# magarray-halleffect-v3r0.net
KiCad netlist of a schematic drawn in EAGLE
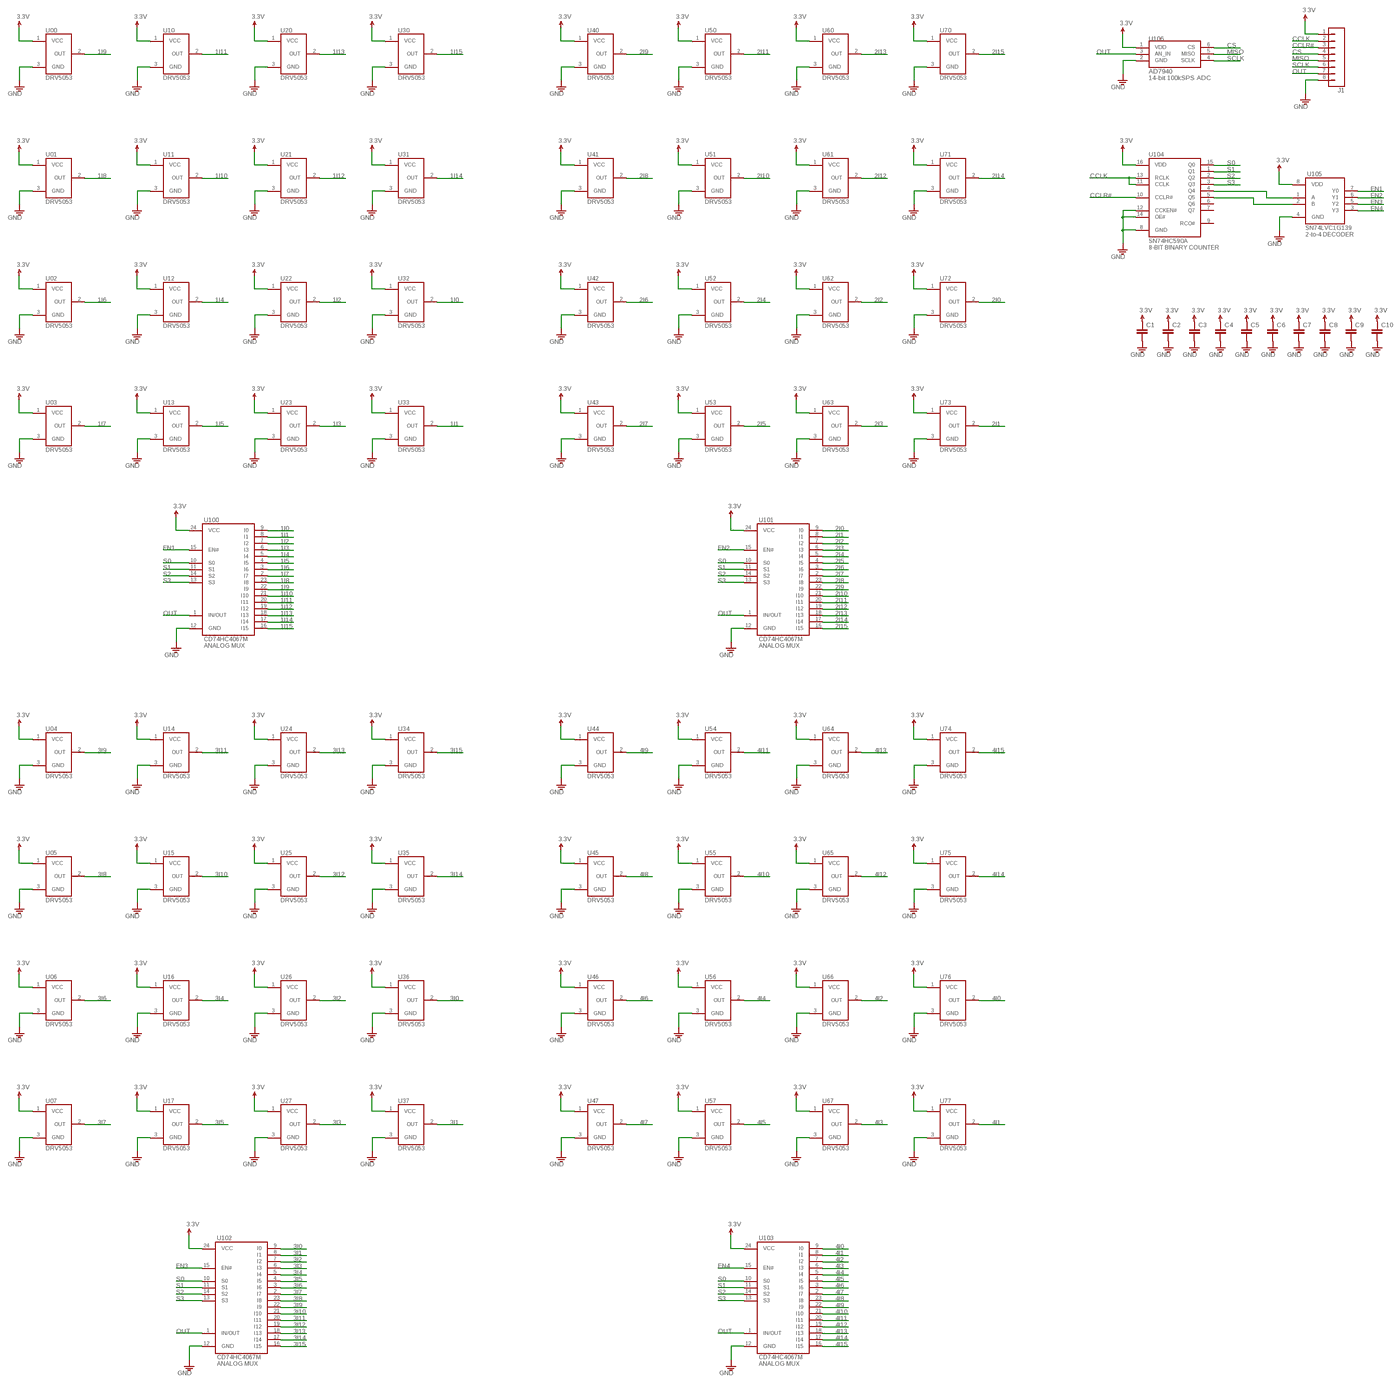
[diagram p0: schematic, sheet 1, overview]
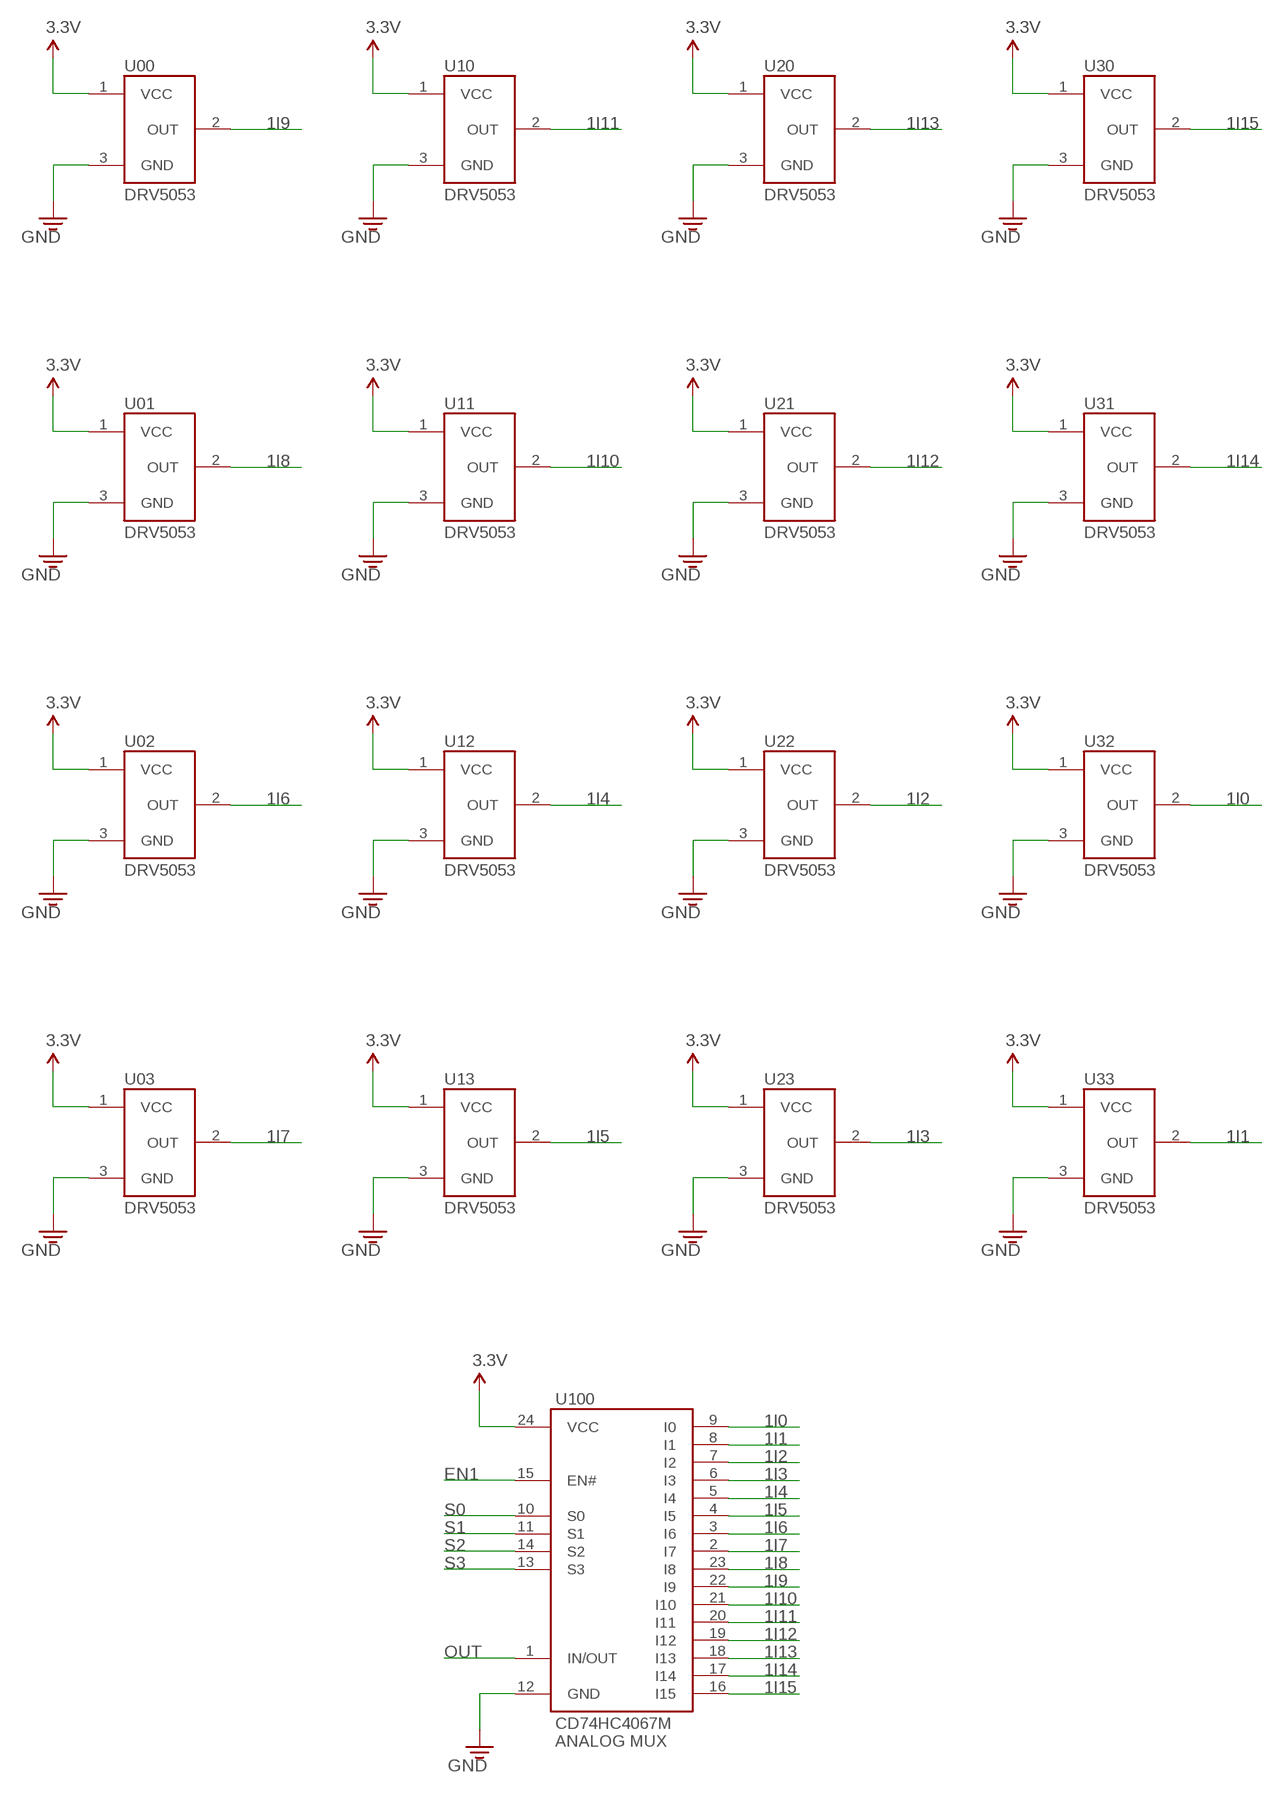
[diagram p1: schematic, sheet 1, part 1 of 4]
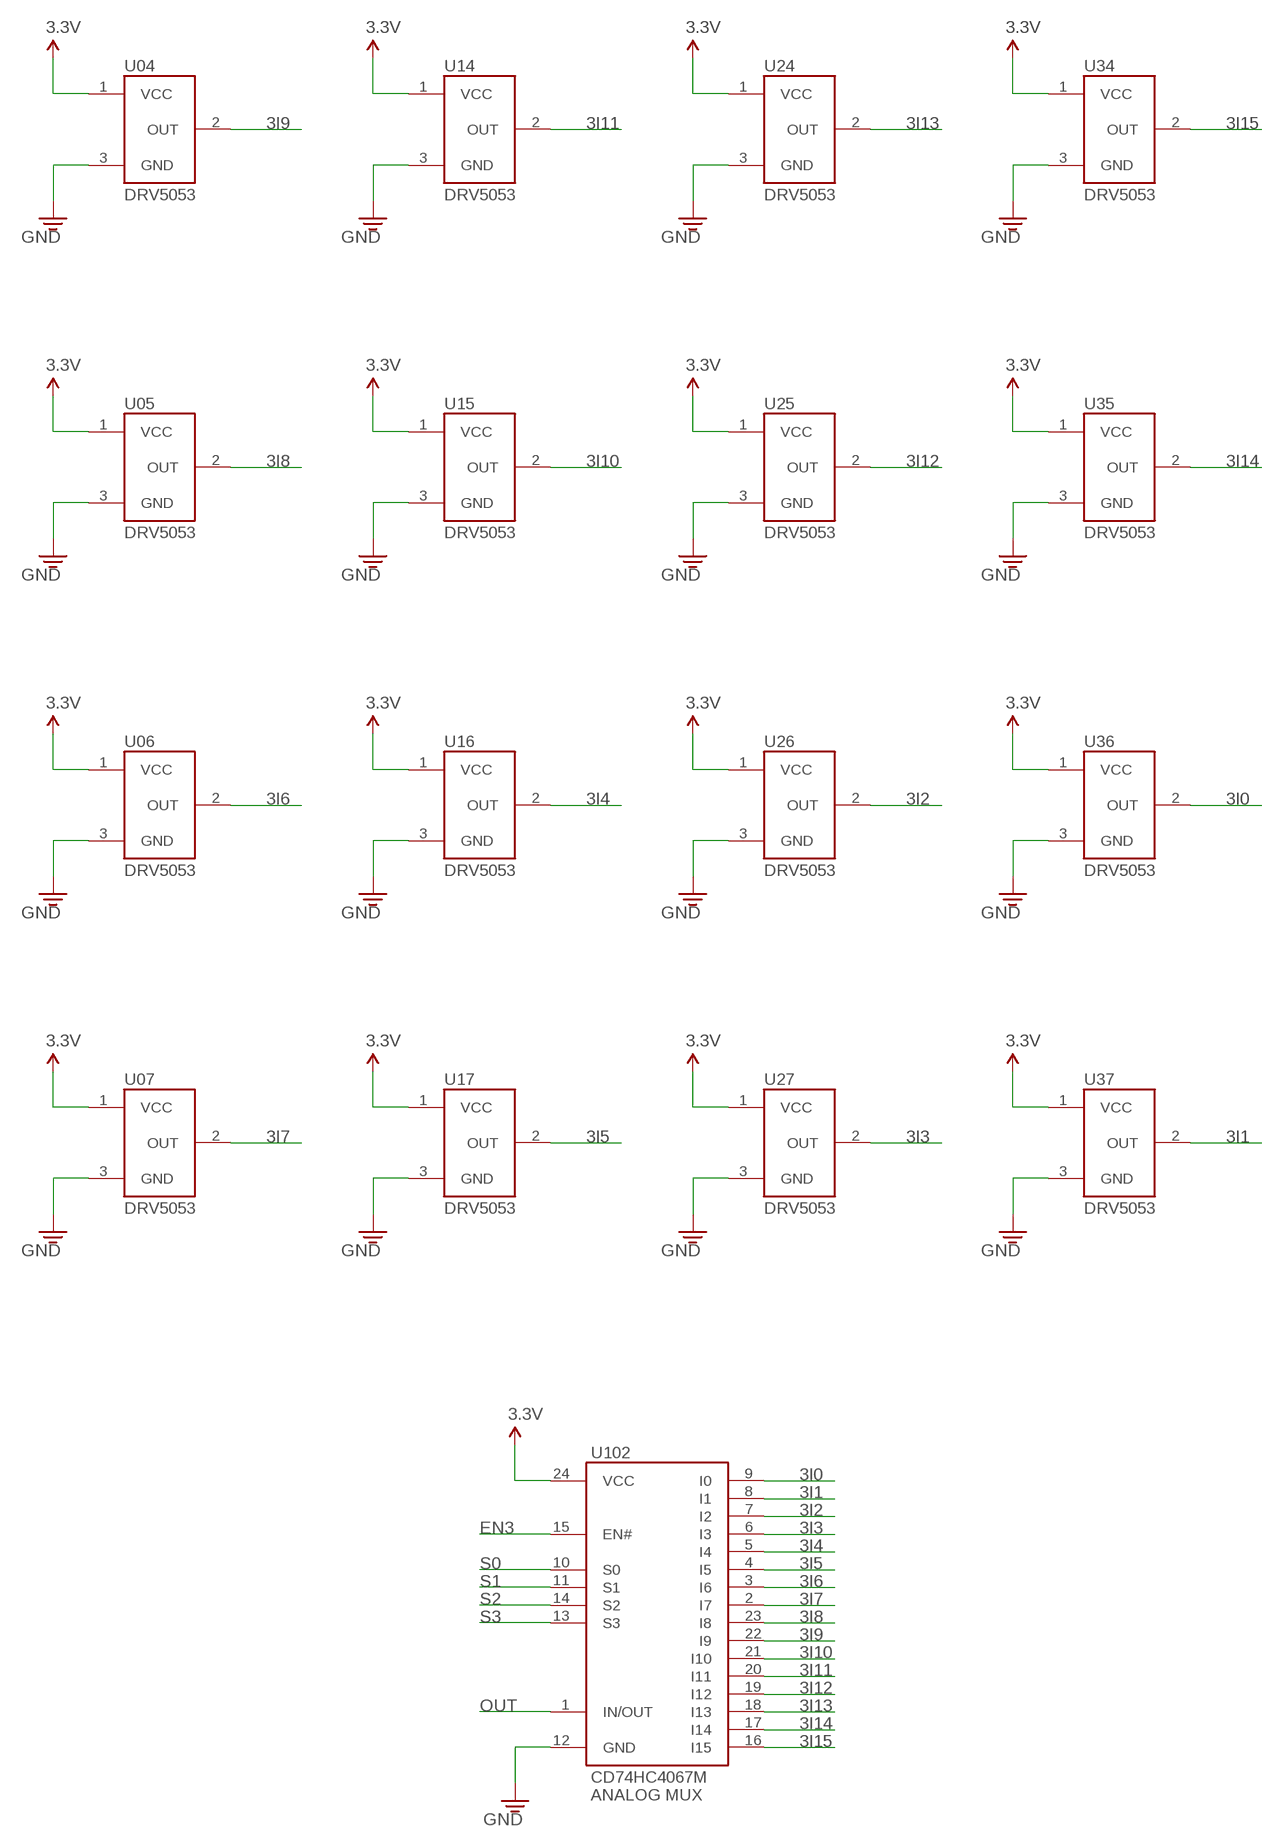
[diagram p2: schematic, sheet 1, part 2 of 4]
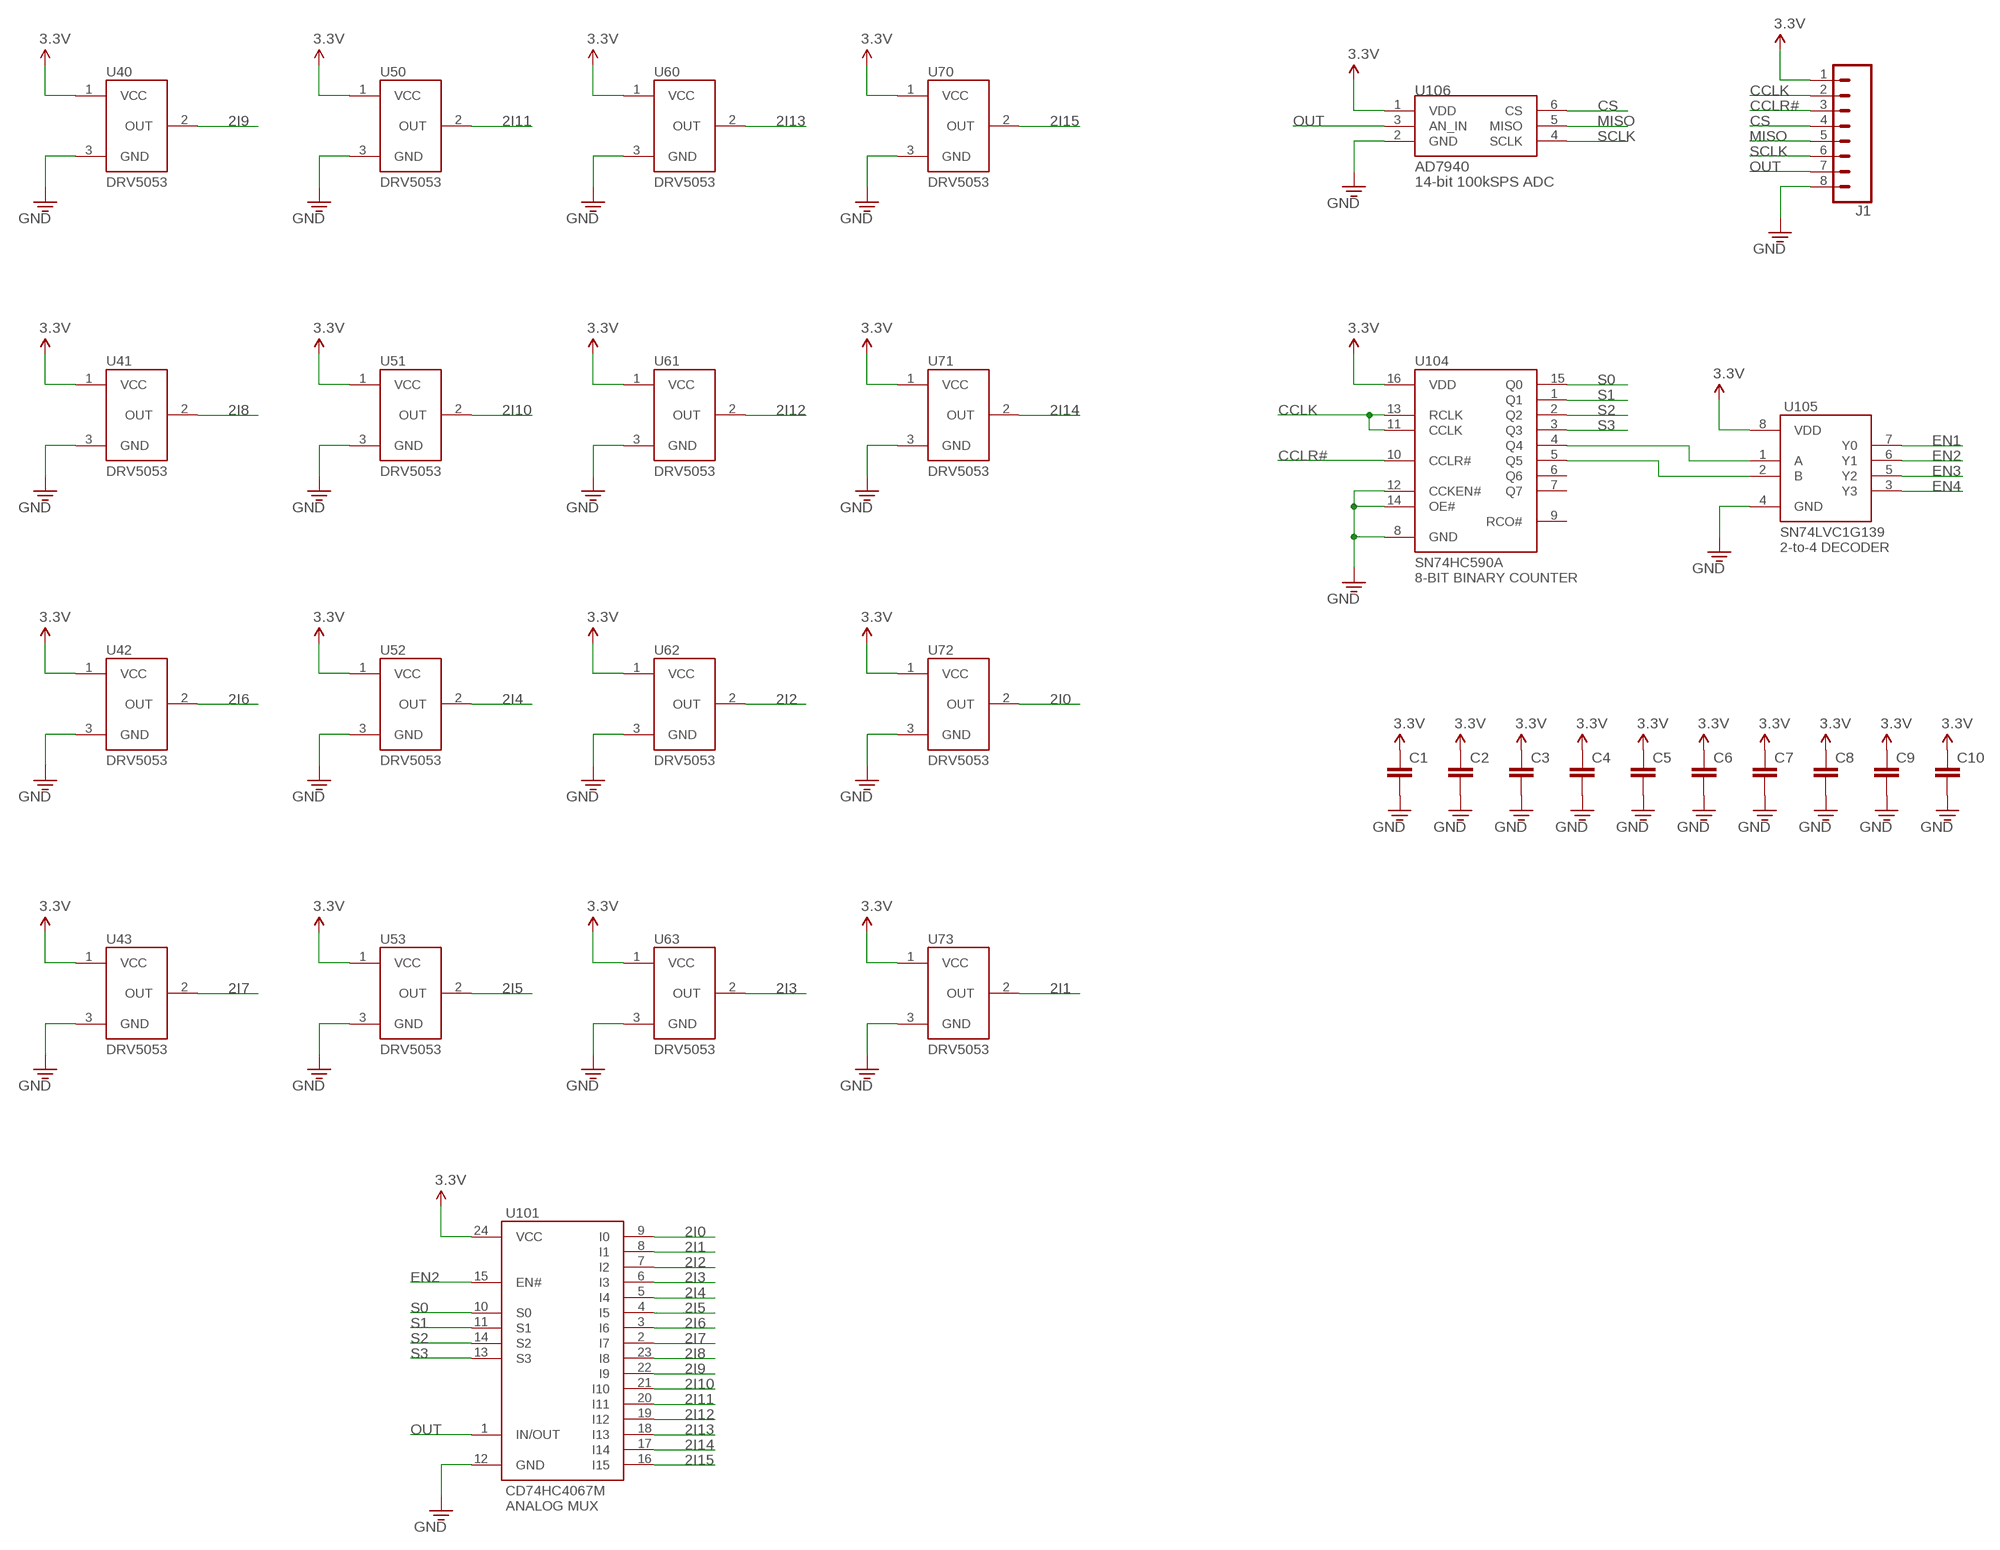
[diagram p3: schematic, sheet 1, part 3 of 4]
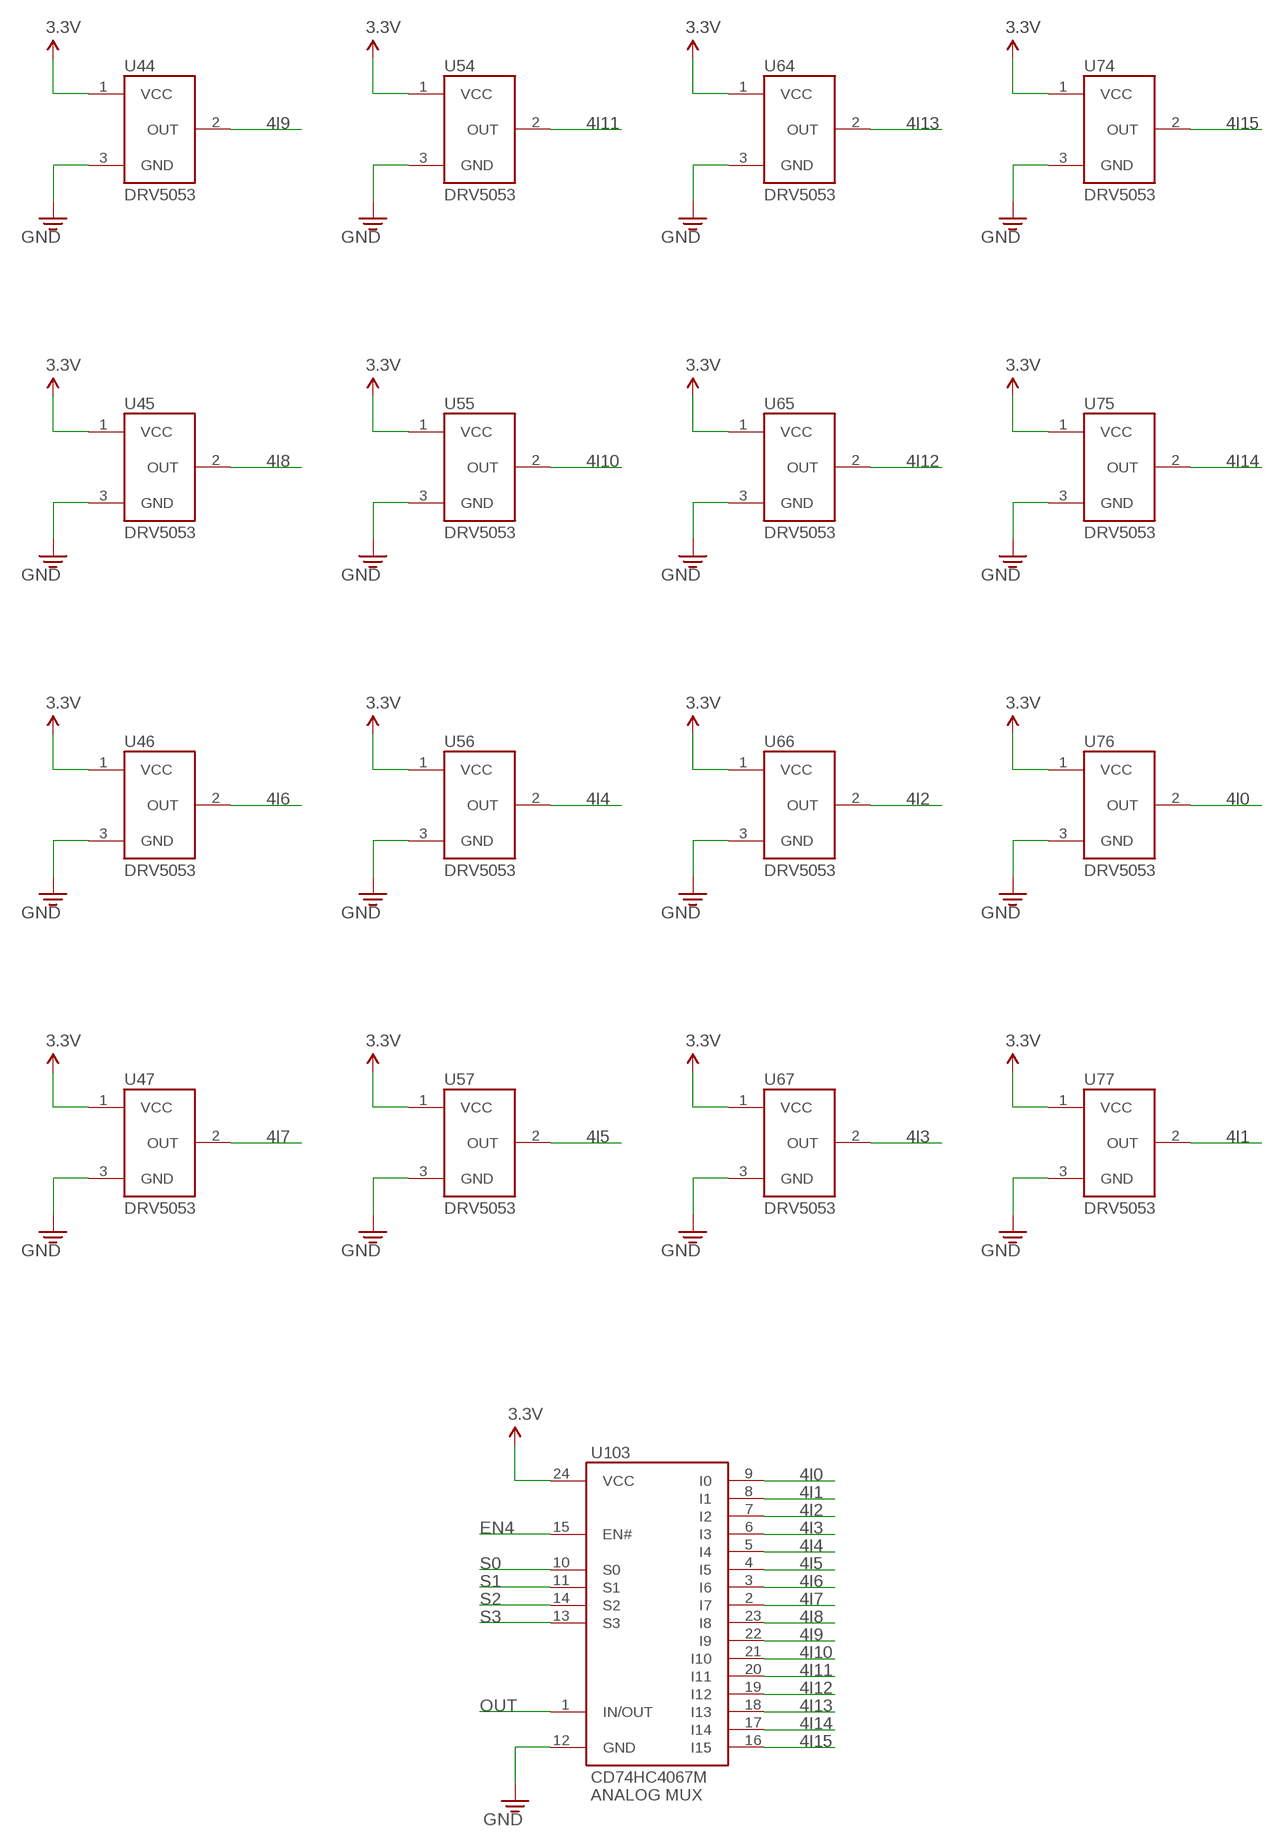
[diagram p4: schematic, sheet 1, part 4 of 4]

(export (version "E")
  (design (tool "Eeschema 10.0.6"))
  (components
    (comp (ref "C1")
      (value "CAP0603")
      (footprint "eagle-import:0603")
      (libsource (lib "eagle-import") (part "CAP0603"))
    )
    (comp (ref "C2")
      (value "CAP0603")
      (footprint "eagle-import:0603")
      (libsource (lib "eagle-import") (part "CAP0603"))
    )
    (comp (ref "C3")
      (value "CAP0603")
      (footprint "eagle-import:0603")
      (libsource (lib "eagle-import") (part "CAP0603"))
    )
    (comp (ref "C4")
      (value "CAP0603")
      (footprint "eagle-import:0603")
      (libsource (lib "eagle-import") (part "CAP0603"))
    )
    (comp (ref "C5")
      (value "CAP0603")
      (footprint "eagle-import:0603")
      (libsource (lib "eagle-import") (part "CAP0603"))
    )
    (comp (ref "C6")
      (value "CAP0603")
      (footprint "eagle-import:0603")
      (libsource (lib "eagle-import") (part "CAP0603"))
    )
    (comp (ref "C7")
      (value "CAP0603")
      (footprint "eagle-import:0603")
      (libsource (lib "eagle-import") (part "CAP0603"))
    )
    (comp (ref "C8")
      (value "CAP0603")
      (footprint "eagle-import:0603")
      (libsource (lib "eagle-import") (part "CAP0603"))
    )
    (comp (ref "C9")
      (value "CAP0603")
      (footprint "eagle-import:0603")
      (libsource (lib "eagle-import") (part "CAP0603"))
    )
    (comp (ref "C10")
      (value "CAP0603")
      (footprint "eagle-import:0603")
      (libsource (lib "eagle-import") (part "CAP0603"))
    )
    (comp (ref "J1")
      (value "CONN_08LOCK_NO_SILK")
      (footprint "eagle-import:1X08_LOCK_NO_SILK")
      (libsource (lib "eagle-import") (part "CONN_08LOCK_NO_SILK"))
    )
    (comp (ref "U00")
      (value "DRV5053")
      (footprint "eagle-import:SOT-23")
      (libsource (lib "eagle-import") (part "DRV5053"))
    )
    (comp (ref "U01")
      (value "DRV5053")
      (footprint "eagle-import:SOT-23")
      (libsource (lib "eagle-import") (part "DRV5053"))
    )
    (comp (ref "U02")
      (value "DRV5053")
      (footprint "eagle-import:SOT-23")
      (libsource (lib "eagle-import") (part "DRV5053"))
    )
    (comp (ref "U03")
      (value "DRV5053")
      (footprint "eagle-import:SOT-23")
      (libsource (lib "eagle-import") (part "DRV5053"))
    )
    (comp (ref "U04")
      (value "DRV5053")
      (footprint "eagle-import:SOT-23")
      (libsource (lib "eagle-import") (part "DRV5053"))
    )
    (comp (ref "U05")
      (value "DRV5053")
      (footprint "eagle-import:SOT-23")
      (libsource (lib "eagle-import") (part "DRV5053"))
    )
    (comp (ref "U06")
      (value "DRV5053")
      (footprint "eagle-import:SOT-23")
      (libsource (lib "eagle-import") (part "DRV5053"))
    )
    (comp (ref "U07")
      (value "DRV5053")
      (footprint "eagle-import:SOT-23")
      (libsource (lib "eagle-import") (part "DRV5053"))
    )
    (comp (ref "U10")
      (value "DRV5053")
      (footprint "eagle-import:SOT-23")
      (libsource (lib "eagle-import") (part "DRV5053"))
    )
    (comp (ref "U11")
      (value "DRV5053")
      (footprint "eagle-import:SOT-23")
      (libsource (lib "eagle-import") (part "DRV5053"))
    )
    (comp (ref "U12")
      (value "DRV5053")
      (footprint "eagle-import:SOT-23")
      (libsource (lib "eagle-import") (part "DRV5053"))
    )
    (comp (ref "U13")
      (value "DRV5053")
      (footprint "eagle-import:SOT-23")
      (libsource (lib "eagle-import") (part "DRV5053"))
    )
    (comp (ref "U14")
      (value "DRV5053")
      (footprint "eagle-import:SOT-23")
      (libsource (lib "eagle-import") (part "DRV5053"))
    )
    (comp (ref "U15")
      (value "DRV5053")
      (footprint "eagle-import:SOT-23")
      (libsource (lib "eagle-import") (part "DRV5053"))
    )
    (comp (ref "U16")
      (value "DRV5053")
      (footprint "eagle-import:SOT-23")
      (libsource (lib "eagle-import") (part "DRV5053"))
    )
    (comp (ref "U17")
      (value "DRV5053")
      (footprint "eagle-import:SOT-23")
      (libsource (lib "eagle-import") (part "DRV5053"))
    )
    (comp (ref "U20")
      (value "DRV5053")
      (footprint "eagle-import:SOT-23")
      (libsource (lib "eagle-import") (part "DRV5053"))
    )
    (comp (ref "U21")
      (value "DRV5053")
      (footprint "eagle-import:SOT-23")
      (libsource (lib "eagle-import") (part "DRV5053"))
    )
    (comp (ref "U22")
      (value "DRV5053")
      (footprint "eagle-import:SOT-23")
      (libsource (lib "eagle-import") (part "DRV5053"))
    )
    (comp (ref "U23")
      (value "DRV5053")
      (footprint "eagle-import:SOT-23")
      (libsource (lib "eagle-import") (part "DRV5053"))
    )
    (comp (ref "U24")
      (value "DRV5053")
      (footprint "eagle-import:SOT-23")
      (libsource (lib "eagle-import") (part "DRV5053"))
    )
    (comp (ref "U25")
      (value "DRV5053")
      (footprint "eagle-import:SOT-23")
      (libsource (lib "eagle-import") (part "DRV5053"))
    )
    (comp (ref "U26")
      (value "DRV5053")
      (footprint "eagle-import:SOT-23")
      (libsource (lib "eagle-import") (part "DRV5053"))
    )
    (comp (ref "U27")
      (value "DRV5053")
      (footprint "eagle-import:SOT-23")
      (libsource (lib "eagle-import") (part "DRV5053"))
    )
    (comp (ref "U30")
      (value "DRV5053")
      (footprint "eagle-import:SOT-23")
      (libsource (lib "eagle-import") (part "DRV5053"))
    )
    (comp (ref "U31")
      (value "DRV5053")
      (footprint "eagle-import:SOT-23")
      (libsource (lib "eagle-import") (part "DRV5053"))
    )
    (comp (ref "U32")
      (value "DRV5053")
      (footprint "eagle-import:SOT-23")
      (libsource (lib "eagle-import") (part "DRV5053"))
    )
    (comp (ref "U33")
      (value "DRV5053")
      (footprint "eagle-import:SOT-23")
      (libsource (lib "eagle-import") (part "DRV5053"))
    )
    (comp (ref "U34")
      (value "DRV5053")
      (footprint "eagle-import:SOT-23")
      (libsource (lib "eagle-import") (part "DRV5053"))
    )
    (comp (ref "U35")
      (value "DRV5053")
      (footprint "eagle-import:SOT-23")
      (libsource (lib "eagle-import") (part "DRV5053"))
    )
    (comp (ref "U36")
      (value "DRV5053")
      (footprint "eagle-import:SOT-23")
      (libsource (lib "eagle-import") (part "DRV5053"))
    )
    (comp (ref "U37")
      (value "DRV5053")
      (footprint "eagle-import:SOT-23")
      (libsource (lib "eagle-import") (part "DRV5053"))
    )
    (comp (ref "U40")
      (value "DRV5053")
      (footprint "eagle-import:SOT-23")
      (libsource (lib "eagle-import") (part "DRV5053"))
    )
    (comp (ref "U41")
      (value "DRV5053")
      (footprint "eagle-import:SOT-23")
      (libsource (lib "eagle-import") (part "DRV5053"))
    )
    (comp (ref "U42")
      (value "DRV5053")
      (footprint "eagle-import:SOT-23")
      (libsource (lib "eagle-import") (part "DRV5053"))
    )
    (comp (ref "U43")
      (value "DRV5053")
      (footprint "eagle-import:SOT-23")
      (libsource (lib "eagle-import") (part "DRV5053"))
    )
    (comp (ref "U44")
      (value "DRV5053")
      (footprint "eagle-import:SOT-23")
      (libsource (lib "eagle-import") (part "DRV5053"))
    )
    (comp (ref "U45")
      (value "DRV5053")
      (footprint "eagle-import:SOT-23")
      (libsource (lib "eagle-import") (part "DRV5053"))
    )
    (comp (ref "U46")
      (value "DRV5053")
      (footprint "eagle-import:SOT-23")
      (libsource (lib "eagle-import") (part "DRV5053"))
    )
    (comp (ref "U47")
      (value "DRV5053")
      (footprint "eagle-import:SOT-23")
      (libsource (lib "eagle-import") (part "DRV5053"))
    )
    (comp (ref "U50")
      (value "DRV5053")
      (footprint "eagle-import:SOT-23")
      (libsource (lib "eagle-import") (part "DRV5053"))
    )
    (comp (ref "U51")
      (value "DRV5053")
      (footprint "eagle-import:SOT-23")
      (libsource (lib "eagle-import") (part "DRV5053"))
    )
    (comp (ref "U52")
      (value "DRV5053")
      (footprint "eagle-import:SOT-23")
      (libsource (lib "eagle-import") (part "DRV5053"))
    )
    (comp (ref "U53")
      (value "DRV5053")
      (footprint "eagle-import:SOT-23")
      (libsource (lib "eagle-import") (part "DRV5053"))
    )
    (comp (ref "U54")
      (value "DRV5053")
      (footprint "eagle-import:SOT-23")
      (libsource (lib "eagle-import") (part "DRV5053"))
    )
    (comp (ref "U55")
      (value "DRV5053")
      (footprint "eagle-import:SOT-23")
      (libsource (lib "eagle-import") (part "DRV5053"))
    )
    (comp (ref "U56")
      (value "DRV5053")
      (footprint "eagle-import:SOT-23")
      (libsource (lib "eagle-import") (part "DRV5053"))
    )
    (comp (ref "U57")
      (value "DRV5053")
      (footprint "eagle-import:SOT-23")
      (libsource (lib "eagle-import") (part "DRV5053"))
    )
    (comp (ref "U60")
      (value "DRV5053")
      (footprint "eagle-import:SOT-23")
      (libsource (lib "eagle-import") (part "DRV5053"))
    )
    (comp (ref "U61")
      (value "DRV5053")
      (footprint "eagle-import:SOT-23")
      (libsource (lib "eagle-import") (part "DRV5053"))
    )
    (comp (ref "U62")
      (value "DRV5053")
      (footprint "eagle-import:SOT-23")
      (libsource (lib "eagle-import") (part "DRV5053"))
    )
    (comp (ref "U63")
      (value "DRV5053")
      (footprint "eagle-import:SOT-23")
      (libsource (lib "eagle-import") (part "DRV5053"))
    )
    (comp (ref "U64")
      (value "DRV5053")
      (footprint "eagle-import:SOT-23")
      (libsource (lib "eagle-import") (part "DRV5053"))
    )
    (comp (ref "U65")
      (value "DRV5053")
      (footprint "eagle-import:SOT-23")
      (libsource (lib "eagle-import") (part "DRV5053"))
    )
    (comp (ref "U66")
      (value "DRV5053")
      (footprint "eagle-import:SOT-23")
      (libsource (lib "eagle-import") (part "DRV5053"))
    )
    (comp (ref "U67")
      (value "DRV5053")
      (footprint "eagle-import:SOT-23")
      (libsource (lib "eagle-import") (part "DRV5053"))
    )
    (comp (ref "U70")
      (value "DRV5053")
      (footprint "eagle-import:SOT-23")
      (libsource (lib "eagle-import") (part "DRV5053"))
    )
    (comp (ref "U71")
      (value "DRV5053")
      (footprint "eagle-import:SOT-23")
      (libsource (lib "eagle-import") (part "DRV5053"))
    )
    (comp (ref "U72")
      (value "DRV5053")
      (footprint "eagle-import:SOT-23")
      (libsource (lib "eagle-import") (part "DRV5053"))
    )
    (comp (ref "U73")
      (value "DRV5053")
      (footprint "eagle-import:SOT-23")
      (libsource (lib "eagle-import") (part "DRV5053"))
    )
    (comp (ref "U74")
      (value "DRV5053")
      (footprint "eagle-import:SOT-23")
      (libsource (lib "eagle-import") (part "DRV5053"))
    )
    (comp (ref "U75")
      (value "DRV5053")
      (footprint "eagle-import:SOT-23")
      (libsource (lib "eagle-import") (part "DRV5053"))
    )
    (comp (ref "U76")
      (value "DRV5053")
      (footprint "eagle-import:SOT-23")
      (libsource (lib "eagle-import") (part "DRV5053"))
    )
    (comp (ref "U77")
      (value "DRV5053")
      (footprint "eagle-import:SOT-23")
      (libsource (lib "eagle-import") (part "DRV5053"))
    )
    (comp (ref "U100")
      (value "CD74HC4067M")
      (footprint "eagle-import:SOIC-24")
      (libsource (lib "eagle-import") (part "CD74HC4067M"))
    )
    (comp (ref "U101")
      (value "CD74HC4067M")
      (footprint "eagle-import:SOIC-24")
      (libsource (lib "eagle-import") (part "CD74HC4067M"))
    )
    (comp (ref "U102")
      (value "CD74HC4067M")
      (footprint "eagle-import:SOIC-24")
      (libsource (lib "eagle-import") (part "CD74HC4067M"))
    )
    (comp (ref "U103")
      (value "CD74HC4067M")
      (footprint "eagle-import:SOIC-24")
      (libsource (lib "eagle-import") (part "CD74HC4067M"))
    )
    (comp (ref "U104")
      (value "SN74HC509A")
      (footprint "eagle-import:SO16")
      (libsource (lib "eagle-import") (part "SN74HC509A"))
    )
    (comp (ref "U105")
      (value "SN74LVC1G139")
      (footprint "eagle-import:SM8")
      (libsource (lib "eagle-import") (part "SN74LVC1G139"))
    )
    (comp (ref "U106")
      (value "AD7940")
      (footprint "eagle-import:SOT-23-6L")
      (libsource (lib "eagle-import") (part "AD7940"))
    )
  )
  (nets
    (net (code "1") (name "/1I0") (class "Default")
      (node (ref "U100") (pin "9") (pinfunction "I0_9") (pintype "bidirectional"))
      (node (ref "U32") (pin "2") (pinfunction "OUT_2") (pintype "bidirectional"))
    )
    (net (code "2") (name "/1I1") (class "Default")
      (node (ref "U100") (pin "8") (pinfunction "I1_8") (pintype "bidirectional"))
      (node (ref "U33") (pin "2") (pinfunction "OUT_2") (pintype "bidirectional"))
    )
    (net (code "3") (name "/1I2") (class "Default")
      (node (ref "U100") (pin "7") (pinfunction "I2_7") (pintype "bidirectional"))
      (node (ref "U22") (pin "2") (pinfunction "OUT_2") (pintype "bidirectional"))
    )
    (net (code "4") (name "/1I3") (class "Default")
      (node (ref "U100") (pin "6") (pinfunction "I3_6") (pintype "bidirectional"))
      (node (ref "U23") (pin "2") (pinfunction "OUT_2") (pintype "bidirectional"))
    )
    (net (code "5") (name "/1I4") (class "Default")
      (node (ref "U100") (pin "5") (pinfunction "I4_5") (pintype "bidirectional"))
      (node (ref "U12") (pin "2") (pinfunction "OUT_2") (pintype "bidirectional"))
    )
    (net (code "6") (name "/1I5") (class "Default")
      (node (ref "U100") (pin "4") (pinfunction "I5_4") (pintype "bidirectional"))
      (node (ref "U13") (pin "2") (pinfunction "OUT_2") (pintype "bidirectional"))
    )
    (net (code "7") (name "/1I6") (class "Default")
      (node (ref "U02") (pin "2") (pinfunction "OUT_2") (pintype "bidirectional"))
      (node (ref "U100") (pin "3") (pinfunction "I6_3") (pintype "bidirectional"))
    )
    (net (code "8") (name "/1I7") (class "Default")
      (node (ref "U03") (pin "2") (pinfunction "OUT_2") (pintype "bidirectional"))
      (node (ref "U100") (pin "2") (pinfunction "I7_2") (pintype "bidirectional"))
    )
    (net (code "9") (name "/1I8") (class "Default")
      (node (ref "U01") (pin "2") (pinfunction "OUT_2") (pintype "bidirectional"))
      (node (ref "U100") (pin "23") (pinfunction "I8_23") (pintype "bidirectional"))
    )
    (net (code "10") (name "/1I9") (class "Default")
      (node (ref "U00") (pin "2") (pinfunction "OUT_2") (pintype "bidirectional"))
      (node (ref "U100") (pin "22") (pinfunction "I9_22") (pintype "bidirectional"))
    )
    (net (code "11") (name "/1I10") (class "Default")
      (node (ref "U100") (pin "21") (pinfunction "I10_21") (pintype "bidirectional"))
      (node (ref "U11") (pin "2") (pinfunction "OUT_2") (pintype "bidirectional"))
    )
    (net (code "12") (name "/1I11") (class "Default")
      (node (ref "U10") (pin "2") (pinfunction "OUT_2") (pintype "bidirectional"))
      (node (ref "U100") (pin "20") (pinfunction "I11_20") (pintype "bidirectional"))
    )
    (net (code "13") (name "/1I12") (class "Default")
      (node (ref "U100") (pin "19") (pinfunction "I12_19") (pintype "bidirectional"))
      (node (ref "U21") (pin "2") (pinfunction "OUT_2") (pintype "bidirectional"))
    )
    (net (code "14") (name "/1I13") (class "Default")
      (node (ref "U100") (pin "18") (pinfunction "I13_18") (pintype "bidirectional"))
      (node (ref "U20") (pin "2") (pinfunction "OUT_2") (pintype "bidirectional"))
    )
    (net (code "15") (name "/1I14") (class "Default")
      (node (ref "U100") (pin "17") (pinfunction "I14_17") (pintype "bidirectional"))
      (node (ref "U31") (pin "2") (pinfunction "OUT_2") (pintype "bidirectional"))
    )
    (net (code "16") (name "/1I15") (class "Default")
      (node (ref "U100") (pin "16") (pinfunction "I15_16") (pintype "bidirectional"))
      (node (ref "U30") (pin "2") (pinfunction "OUT_2") (pintype "bidirectional"))
    )
    (net (code "17") (name "/2I0") (class "Default")
      (node (ref "U101") (pin "9") (pinfunction "I0_9") (pintype "bidirectional"))
      (node (ref "U72") (pin "2") (pinfunction "OUT_2") (pintype "bidirectional"))
    )
    (net (code "18") (name "/2I1") (class "Default")
      (node (ref "U101") (pin "8") (pinfunction "I1_8") (pintype "bidirectional"))
      (node (ref "U73") (pin "2") (pinfunction "OUT_2") (pintype "bidirectional"))
    )
    (net (code "19") (name "/2I2") (class "Default")
      (node (ref "U101") (pin "7") (pinfunction "I2_7") (pintype "bidirectional"))
      (node (ref "U62") (pin "2") (pinfunction "OUT_2") (pintype "bidirectional"))
    )
    (net (code "20") (name "/2I3") (class "Default")
      (node (ref "U101") (pin "6") (pinfunction "I3_6") (pintype "bidirectional"))
      (node (ref "U63") (pin "2") (pinfunction "OUT_2") (pintype "bidirectional"))
    )
    (net (code "21") (name "/2I4") (class "Default")
      (node (ref "U101") (pin "5") (pinfunction "I4_5") (pintype "bidirectional"))
      (node (ref "U52") (pin "2") (pinfunction "OUT_2") (pintype "bidirectional"))
    )
    (net (code "22") (name "/2I5") (class "Default")
      (node (ref "U101") (pin "4") (pinfunction "I5_4") (pintype "bidirectional"))
      (node (ref "U53") (pin "2") (pinfunction "OUT_2") (pintype "bidirectional"))
    )
    (net (code "23") (name "/2I6") (class "Default")
      (node (ref "U101") (pin "3") (pinfunction "I6_3") (pintype "bidirectional"))
      (node (ref "U42") (pin "2") (pinfunction "OUT_2") (pintype "bidirectional"))
    )
    (net (code "24") (name "/2I7") (class "Default")
      (node (ref "U101") (pin "2") (pinfunction "I7_2") (pintype "bidirectional"))
      (node (ref "U43") (pin "2") (pinfunction "OUT_2") (pintype "bidirectional"))
    )
    (net (code "25") (name "/2I8") (class "Default")
      (node (ref "U101") (pin "23") (pinfunction "I8_23") (pintype "bidirectional"))
      (node (ref "U41") (pin "2") (pinfunction "OUT_2") (pintype "bidirectional"))
    )
    (net (code "26") (name "/2I9") (class "Default")
      (node (ref "U101") (pin "22") (pinfunction "I9_22") (pintype "bidirectional"))
      (node (ref "U40") (pin "2") (pinfunction "OUT_2") (pintype "bidirectional"))
    )
    (net (code "27") (name "/2I10") (class "Default")
      (node (ref "U101") (pin "21") (pinfunction "I10_21") (pintype "bidirectional"))
      (node (ref "U51") (pin "2") (pinfunction "OUT_2") (pintype "bidirectional"))
    )
    (net (code "28") (name "/2I11") (class "Default")
      (node (ref "U101") (pin "20") (pinfunction "I11_20") (pintype "bidirectional"))
      (node (ref "U50") (pin "2") (pinfunction "OUT_2") (pintype "bidirectional"))
    )
    (net (code "29") (name "/2I12") (class "Default")
      (node (ref "U101") (pin "19") (pinfunction "I12_19") (pintype "bidirectional"))
      (node (ref "U61") (pin "2") (pinfunction "OUT_2") (pintype "bidirectional"))
    )
    (net (code "30") (name "/2I13") (class "Default")
      (node (ref "U101") (pin "18") (pinfunction "I13_18") (pintype "bidirectional"))
      (node (ref "U60") (pin "2") (pinfunction "OUT_2") (pintype "bidirectional"))
    )
    (net (code "31") (name "/2I14") (class "Default")
      (node (ref "U101") (pin "17") (pinfunction "I14_17") (pintype "bidirectional"))
      (node (ref "U71") (pin "2") (pinfunction "OUT_2") (pintype "bidirectional"))
    )
    (net (code "32") (name "/2I15") (class "Default")
      (node (ref "U101") (pin "16") (pinfunction "I15_16") (pintype "bidirectional"))
      (node (ref "U70") (pin "2") (pinfunction "OUT_2") (pintype "bidirectional"))
    )
    (net (code "33") (name "/3I0") (class "Default")
      (node (ref "U102") (pin "9") (pinfunction "I0_9") (pintype "bidirectional"))
      (node (ref "U36") (pin "2") (pinfunction "OUT_2") (pintype "bidirectional"))
    )
    (net (code "34") (name "/3I1") (class "Default")
      (node (ref "U102") (pin "8") (pinfunction "I1_8") (pintype "bidirectional"))
      (node (ref "U37") (pin "2") (pinfunction "OUT_2") (pintype "bidirectional"))
    )
    (net (code "35") (name "/3I2") (class "Default")
      (node (ref "U102") (pin "7") (pinfunction "I2_7") (pintype "bidirectional"))
      (node (ref "U26") (pin "2") (pinfunction "OUT_2") (pintype "bidirectional"))
    )
    (net (code "36") (name "/3I3") (class "Default")
      (node (ref "U102") (pin "6") (pinfunction "I3_6") (pintype "bidirectional"))
      (node (ref "U27") (pin "2") (pinfunction "OUT_2") (pintype "bidirectional"))
    )
    (net (code "37") (name "/3I4") (class "Default")
      (node (ref "U102") (pin "5") (pinfunction "I4_5") (pintype "bidirectional"))
      (node (ref "U16") (pin "2") (pinfunction "OUT_2") (pintype "bidirectional"))
    )
    (net (code "38") (name "/3I5") (class "Default")
      (node (ref "U102") (pin "4") (pinfunction "I5_4") (pintype "bidirectional"))
      (node (ref "U17") (pin "2") (pinfunction "OUT_2") (pintype "bidirectional"))
    )
    (net (code "39") (name "/3I6") (class "Default")
      (node (ref "U06") (pin "2") (pinfunction "OUT_2") (pintype "bidirectional"))
      (node (ref "U102") (pin "3") (pinfunction "I6_3") (pintype "bidirectional"))
    )
    (net (code "40") (name "/3I7") (class "Default")
      (node (ref "U07") (pin "2") (pinfunction "OUT_2") (pintype "bidirectional"))
      (node (ref "U102") (pin "2") (pinfunction "I7_2") (pintype "bidirectional"))
    )
    (net (code "41") (name "/3I8") (class "Default")
      (node (ref "U05") (pin "2") (pinfunction "OUT_2") (pintype "bidirectional"))
      (node (ref "U102") (pin "23") (pinfunction "I8_23") (pintype "bidirectional"))
    )
    (net (code "42") (name "/3I9") (class "Default")
      (node (ref "U04") (pin "2") (pinfunction "OUT_2") (pintype "bidirectional"))
      (node (ref "U102") (pin "22") (pinfunction "I9_22") (pintype "bidirectional"))
    )
    (net (code "43") (name "/3I10") (class "Default")
      (node (ref "U102") (pin "21") (pinfunction "I10_21") (pintype "bidirectional"))
      (node (ref "U15") (pin "2") (pinfunction "OUT_2") (pintype "bidirectional"))
    )
    (net (code "44") (name "/3I11") (class "Default")
      (node (ref "U102") (pin "20") (pinfunction "I11_20") (pintype "bidirectional"))
      (node (ref "U14") (pin "2") (pinfunction "OUT_2") (pintype "bidirectional"))
    )
    (net (code "45") (name "/3I12") (class "Default")
      (node (ref "U102") (pin "19") (pinfunction "I12_19") (pintype "bidirectional"))
      (node (ref "U25") (pin "2") (pinfunction "OUT_2") (pintype "bidirectional"))
    )
    (net (code "46") (name "/3I13") (class "Default")
      (node (ref "U102") (pin "18") (pinfunction "I13_18") (pintype "bidirectional"))
      (node (ref "U24") (pin "2") (pinfunction "OUT_2") (pintype "bidirectional"))
    )
    (net (code "47") (name "/3I14") (class "Default")
      (node (ref "U102") (pin "17") (pinfunction "I14_17") (pintype "bidirectional"))
      (node (ref "U35") (pin "2") (pinfunction "OUT_2") (pintype "bidirectional"))
    )
    (net (code "48") (name "/3I15") (class "Default")
      (node (ref "U102") (pin "16") (pinfunction "I15_16") (pintype "bidirectional"))
      (node (ref "U34") (pin "2") (pinfunction "OUT_2") (pintype "bidirectional"))
    )
    (net (code "49") (name "/4I0") (class "Default")
      (node (ref "U103") (pin "9") (pinfunction "I0_9") (pintype "bidirectional"))
      (node (ref "U76") (pin "2") (pinfunction "OUT_2") (pintype "bidirectional"))
    )
    (net (code "50") (name "/4I1") (class "Default")
      (node (ref "U103") (pin "8") (pinfunction "I1_8") (pintype "bidirectional"))
      (node (ref "U77") (pin "2") (pinfunction "OUT_2") (pintype "bidirectional"))
    )
    (net (code "51") (name "/4I2") (class "Default")
      (node (ref "U103") (pin "7") (pinfunction "I2_7") (pintype "bidirectional"))
      (node (ref "U66") (pin "2") (pinfunction "OUT_2") (pintype "bidirectional"))
    )
    (net (code "52") (name "/4I3") (class "Default")
      (node (ref "U103") (pin "6") (pinfunction "I3_6") (pintype "bidirectional"))
      (node (ref "U67") (pin "2") (pinfunction "OUT_2") (pintype "bidirectional"))
    )
    (net (code "53") (name "/4I4") (class "Default")
      (node (ref "U103") (pin "5") (pinfunction "I4_5") (pintype "bidirectional"))
      (node (ref "U56") (pin "2") (pinfunction "OUT_2") (pintype "bidirectional"))
    )
    (net (code "54") (name "/4I5") (class "Default")
      (node (ref "U103") (pin "4") (pinfunction "I5_4") (pintype "bidirectional"))
      (node (ref "U57") (pin "2") (pinfunction "OUT_2") (pintype "bidirectional"))
    )
    (net (code "55") (name "/4I6") (class "Default")
      (node (ref "U103") (pin "3") (pinfunction "I6_3") (pintype "bidirectional"))
      (node (ref "U46") (pin "2") (pinfunction "OUT_2") (pintype "bidirectional"))
    )
    (net (code "56") (name "/4I7") (class "Default")
      (node (ref "U103") (pin "2") (pinfunction "I7_2") (pintype "bidirectional"))
      (node (ref "U47") (pin "2") (pinfunction "OUT_2") (pintype "bidirectional"))
    )
    (net (code "57") (name "/4I8") (class "Default")
      (node (ref "U103") (pin "23") (pinfunction "I8_23") (pintype "bidirectional"))
      (node (ref "U45") (pin "2") (pinfunction "OUT_2") (pintype "bidirectional"))
    )
    (net (code "58") (name "/4I9") (class "Default")
      (node (ref "U103") (pin "22") (pinfunction "I9_22") (pintype "bidirectional"))
      (node (ref "U44") (pin "2") (pinfunction "OUT_2") (pintype "bidirectional"))
    )
    (net (code "59") (name "/4I10") (class "Default")
      (node (ref "U103") (pin "21") (pinfunction "I10_21") (pintype "bidirectional"))
      (node (ref "U55") (pin "2") (pinfunction "OUT_2") (pintype "bidirectional"))
    )
    (net (code "60") (name "/4I11") (class "Default")
      (node (ref "U103") (pin "20") (pinfunction "I11_20") (pintype "bidirectional"))
      (node (ref "U54") (pin "2") (pinfunction "OUT_2") (pintype "bidirectional"))
    )
    (net (code "61") (name "/4I12") (class "Default")
      (node (ref "U103") (pin "19") (pinfunction "I12_19") (pintype "bidirectional"))
      (node (ref "U65") (pin "2") (pinfunction "OUT_2") (pintype "bidirectional"))
    )
    (net (code "62") (name "/4I13") (class "Default")
      (node (ref "U103") (pin "18") (pinfunction "I13_18") (pintype "bidirectional"))
      (node (ref "U64") (pin "2") (pinfunction "OUT_2") (pintype "bidirectional"))
    )
    (net (code "63") (name "/4I14") (class "Default")
      (node (ref "U103") (pin "17") (pinfunction "I14_17") (pintype "bidirectional"))
      (node (ref "U75") (pin "2") (pinfunction "OUT_2") (pintype "bidirectional"))
    )
    (net (code "64") (name "/4I15") (class "Default")
      (node (ref "U103") (pin "16") (pinfunction "I15_16") (pintype "bidirectional"))
      (node (ref "U74") (pin "2") (pinfunction "OUT_2") (pintype "bidirectional"))
    )
    (net (code "65") (name "/CCLK") (class "Default")
      (node (ref "J1") (pin "2") (pinfunction "2_2") (pintype "passive"))
      (node (ref "U104") (pin "11") (pinfunction "CCLK_11") (pintype "bidirectional"))
      (node (ref "U104") (pin "13") (pinfunction "RCLK_13") (pintype "bidirectional"))
    )
    (net (code "66") (name "/CCLR#") (class "Default")
      (node (ref "J1") (pin "3") (pinfunction "3_3") (pintype "passive"))
      (node (ref "U104") (pin "10") (pinfunction "CCLR#_10") (pintype "bidirectional"))
    )
    (net (code "67") (name "/CS") (class "Default")
      (node (ref "J1") (pin "4") (pinfunction "4_4") (pintype "passive"))
      (node (ref "U106") (pin "6") (pinfunction "CS_6") (pintype "bidirectional"))
    )
    (net (code "68") (name "/EN1") (class "Default")
      (node (ref "U100") (pin "15") (pinfunction "EN#_15") (pintype "bidirectional"))
      (node (ref "U105") (pin "7") (pinfunction "Y0_7") (pintype "bidirectional"))
    )
    (net (code "69") (name "/EN2") (class "Default")
      (node (ref "U101") (pin "15") (pinfunction "EN#_15") (pintype "bidirectional"))
      (node (ref "U105") (pin "6") (pinfunction "Y1_6") (pintype "bidirectional"))
    )
    (net (code "70") (name "/EN3") (class "Default")
      (node (ref "U102") (pin "15") (pinfunction "EN#_15") (pintype "bidirectional"))
      (node (ref "U105") (pin "5") (pinfunction "Y2_5") (pintype "bidirectional"))
    )
    (net (code "71") (name "/EN4") (class "Default")
      (node (ref "U103") (pin "15") (pinfunction "EN#_15") (pintype "bidirectional"))
      (node (ref "U105") (pin "3") (pinfunction "Y3_3") (pintype "bidirectional"))
    )
    (net (code "72") (name "/MISO") (class "Default")
      (node (ref "J1") (pin "5") (pinfunction "5_5") (pintype "passive"))
      (node (ref "U106") (pin "5") (pinfunction "MISO_5") (pintype "bidirectional"))
    )
    (net (code "73") (name "/OUT") (class "Default")
      (node (ref "J1") (pin "7") (pinfunction "7_7") (pintype "passive"))
      (node (ref "U100") (pin "1") (pinfunction "IN/OUT_1") (pintype "bidirectional"))
      (node (ref "U101") (pin "1") (pinfunction "IN/OUT_1") (pintype "bidirectional"))
      (node (ref "U102") (pin "1") (pinfunction "IN/OUT_1") (pintype "bidirectional"))
      (node (ref "U103") (pin "1") (pinfunction "IN/OUT_1") (pintype "bidirectional"))
      (node (ref "U106") (pin "3") (pinfunction "AN_IN_3") (pintype "bidirectional"))
    )
    (net (code "74") (name "/S0") (class "Default")
      (node (ref "U100") (pin "10") (pinfunction "S0_10") (pintype "bidirectional"))
      (node (ref "U101") (pin "10") (pinfunction "S0_10") (pintype "bidirectional"))
      (node (ref "U102") (pin "10") (pinfunction "S0_10") (pintype "bidirectional"))
      (node (ref "U103") (pin "10") (pinfunction "S0_10") (pintype "bidirectional"))
      (node (ref "U104") (pin "15") (pinfunction "Q0_15") (pintype "bidirectional"))
    )
    (net (code "75") (name "/S1") (class "Default")
      (node (ref "U100") (pin "11") (pinfunction "S1_11") (pintype "bidirectional"))
      (node (ref "U101") (pin "11") (pinfunction "S1_11") (pintype "bidirectional"))
      (node (ref "U102") (pin "11") (pinfunction "S1_11") (pintype "bidirectional"))
      (node (ref "U103") (pin "11") (pinfunction "S1_11") (pintype "bidirectional"))
      (node (ref "U104") (pin "1") (pinfunction "Q1_1") (pintype "bidirectional"))
    )
    (net (code "76") (name "/S2") (class "Default")
      (node (ref "U100") (pin "14") (pinfunction "S2_14") (pintype "bidirectional"))
      (node (ref "U101") (pin "14") (pinfunction "S2_14") (pintype "bidirectional"))
      (node (ref "U102") (pin "14") (pinfunction "S2_14") (pintype "bidirectional"))
      (node (ref "U103") (pin "14") (pinfunction "S2_14") (pintype "bidirectional"))
      (node (ref "U104") (pin "2") (pinfunction "Q2_2") (pintype "bidirectional"))
    )
    (net (code "77") (name "/S3") (class "Default")
      (node (ref "U100") (pin "13") (pinfunction "S3_13") (pintype "bidirectional"))
      (node (ref "U101") (pin "13") (pinfunction "S3_13") (pintype "bidirectional"))
      (node (ref "U102") (pin "13") (pinfunction "S3_13") (pintype "bidirectional"))
      (node (ref "U103") (pin "13") (pinfunction "S3_13") (pintype "bidirectional"))
      (node (ref "U104") (pin "3") (pinfunction "Q3_3") (pintype "bidirectional"))
    )
    (net (code "78") (name "/SCLK") (class "Default")
      (node (ref "J1") (pin "6") (pinfunction "6_6") (pintype "passive"))
      (node (ref "U106") (pin "4") (pinfunction "SCLK_4") (pintype "bidirectional"))
    )
    (net (code "79") (name "3.3V") (class "Default")
      (node (ref "C1") (pin "1") (pinfunction "1_1") (pintype "passive"))
      (node (ref "C10") (pin "1") (pinfunction "1_1") (pintype "passive"))
      (node (ref "C2") (pin "1") (pinfunction "1_1") (pintype "passive"))
      (node (ref "C3") (pin "1") (pinfunction "1_1") (pintype "passive"))
      (node (ref "C4") (pin "1") (pinfunction "1_1") (pintype "passive"))
      (node (ref "C5") (pin "1") (pinfunction "1_1") (pintype "passive"))
      (node (ref "C6") (pin "1") (pinfunction "1_1") (pintype "passive"))
      (node (ref "C7") (pin "1") (pinfunction "1_1") (pintype "passive"))
      (node (ref "C8") (pin "1") (pinfunction "1_1") (pintype "passive"))
      (node (ref "C9") (pin "1") (pinfunction "1_1") (pintype "passive"))
      (node (ref "J1") (pin "1") (pinfunction "1_1") (pintype "passive"))
      (node (ref "U00") (pin "1") (pinfunction "VCC_1") (pintype "bidirectional"))
      (node (ref "U01") (pin "1") (pinfunction "VCC_1") (pintype "bidirectional"))
      (node (ref "U02") (pin "1") (pinfunction "VCC_1") (pintype "bidirectional"))
      (node (ref "U03") (pin "1") (pinfunction "VCC_1") (pintype "bidirectional"))
      (node (ref "U04") (pin "1") (pinfunction "VCC_1") (pintype "bidirectional"))
      (node (ref "U05") (pin "1") (pinfunction "VCC_1") (pintype "bidirectional"))
      (node (ref "U06") (pin "1") (pinfunction "VCC_1") (pintype "bidirectional"))
      (node (ref "U07") (pin "1") (pinfunction "VCC_1") (pintype "bidirectional"))
      (node (ref "U10") (pin "1") (pinfunction "VCC_1") (pintype "bidirectional"))
      (node (ref "U100") (pin "24") (pinfunction "VCC_24") (pintype "bidirectional"))
      (node (ref "U101") (pin "24") (pinfunction "VCC_24") (pintype "bidirectional"))
      (node (ref "U102") (pin "24") (pinfunction "VCC_24") (pintype "bidirectional"))
      (node (ref "U103") (pin "24") (pinfunction "VCC_24") (pintype "bidirectional"))
      (node (ref "U104") (pin "16") (pinfunction "VDD_16") (pintype "bidirectional"))
      (node (ref "U105") (pin "8") (pinfunction "VDD_8") (pintype "bidirectional"))
      (node (ref "U106") (pin "1") (pinfunction "VDD_1") (pintype "bidirectional"))
      (node (ref "U11") (pin "1") (pinfunction "VCC_1") (pintype "bidirectional"))
      (node (ref "U12") (pin "1") (pinfunction "VCC_1") (pintype "bidirectional"))
      (node (ref "U13") (pin "1") (pinfunction "VCC_1") (pintype "bidirectional"))
      (node (ref "U14") (pin "1") (pinfunction "VCC_1") (pintype "bidirectional"))
      (node (ref "U15") (pin "1") (pinfunction "VCC_1") (pintype "bidirectional"))
      (node (ref "U16") (pin "1") (pinfunction "VCC_1") (pintype "bidirectional"))
      (node (ref "U17") (pin "1") (pinfunction "VCC_1") (pintype "bidirectional"))
      (node (ref "U20") (pin "1") (pinfunction "VCC_1") (pintype "bidirectional"))
      (node (ref "U21") (pin "1") (pinfunction "VCC_1") (pintype "bidirectional"))
      (node (ref "U22") (pin "1") (pinfunction "VCC_1") (pintype "bidirectional"))
      (node (ref "U23") (pin "1") (pinfunction "VCC_1") (pintype "bidirectional"))
      (node (ref "U24") (pin "1") (pinfunction "VCC_1") (pintype "bidirectional"))
      (node (ref "U25") (pin "1") (pinfunction "VCC_1") (pintype "bidirectional"))
      (node (ref "U26") (pin "1") (pinfunction "VCC_1") (pintype "bidirectional"))
      (node (ref "U27") (pin "1") (pinfunction "VCC_1") (pintype "bidirectional"))
      (node (ref "U30") (pin "1") (pinfunction "VCC_1") (pintype "bidirectional"))
      (node (ref "U31") (pin "1") (pinfunction "VCC_1") (pintype "bidirectional"))
      (node (ref "U32") (pin "1") (pinfunction "VCC_1") (pintype "bidirectional"))
      (node (ref "U33") (pin "1") (pinfunction "VCC_1") (pintype "bidirectional"))
      (node (ref "U34") (pin "1") (pinfunction "VCC_1") (pintype "bidirectional"))
      (node (ref "U35") (pin "1") (pinfunction "VCC_1") (pintype "bidirectional"))
      (node (ref "U36") (pin "1") (pinfunction "VCC_1") (pintype "bidirectional"))
      (node (ref "U37") (pin "1") (pinfunction "VCC_1") (pintype "bidirectional"))
      (node (ref "U40") (pin "1") (pinfunction "VCC_1") (pintype "bidirectional"))
      (node (ref "U41") (pin "1") (pinfunction "VCC_1") (pintype "bidirectional"))
      (node (ref "U42") (pin "1") (pinfunction "VCC_1") (pintype "bidirectional"))
      (node (ref "U43") (pin "1") (pinfunction "VCC_1") (pintype "bidirectional"))
      (node (ref "U44") (pin "1") (pinfunction "VCC_1") (pintype "bidirectional"))
      (node (ref "U45") (pin "1") (pinfunction "VCC_1") (pintype "bidirectional"))
      (node (ref "U46") (pin "1") (pinfunction "VCC_1") (pintype "bidirectional"))
      (node (ref "U47") (pin "1") (pinfunction "VCC_1") (pintype "bidirectional"))
      (node (ref "U50") (pin "1") (pinfunction "VCC_1") (pintype "bidirectional"))
      (node (ref "U51") (pin "1") (pinfunction "VCC_1") (pintype "bidirectional"))
      (node (ref "U52") (pin "1") (pinfunction "VCC_1") (pintype "bidirectional"))
      (node (ref "U53") (pin "1") (pinfunction "VCC_1") (pintype "bidirectional"))
      (node (ref "U54") (pin "1") (pinfunction "VCC_1") (pintype "bidirectional"))
      (node (ref "U55") (pin "1") (pinfunction "VCC_1") (pintype "bidirectional"))
      (node (ref "U56") (pin "1") (pinfunction "VCC_1") (pintype "bidirectional"))
      (node (ref "U57") (pin "1") (pinfunction "VCC_1") (pintype "bidirectional"))
      (node (ref "U60") (pin "1") (pinfunction "VCC_1") (pintype "bidirectional"))
      (node (ref "U61") (pin "1") (pinfunction "VCC_1") (pintype "bidirectional"))
      (node (ref "U62") (pin "1") (pinfunction "VCC_1") (pintype "bidirectional"))
      (node (ref "U63") (pin "1") (pinfunction "VCC_1") (pintype "bidirectional"))
      (node (ref "U64") (pin "1") (pinfunction "VCC_1") (pintype "bidirectional"))
      (node (ref "U65") (pin "1") (pinfunction "VCC_1") (pintype "bidirectional"))
      (node (ref "U66") (pin "1") (pinfunction "VCC_1") (pintype "bidirectional"))
      (node (ref "U67") (pin "1") (pinfunction "VCC_1") (pintype "bidirectional"))
      (node (ref "U70") (pin "1") (pinfunction "VCC_1") (pintype "bidirectional"))
      (node (ref "U71") (pin "1") (pinfunction "VCC_1") (pintype "bidirectional"))
      (node (ref "U72") (pin "1") (pinfunction "VCC_1") (pintype "bidirectional"))
      (node (ref "U73") (pin "1") (pinfunction "VCC_1") (pintype "bidirectional"))
      (node (ref "U74") (pin "1") (pinfunction "VCC_1") (pintype "bidirectional"))
      (node (ref "U75") (pin "1") (pinfunction "VCC_1") (pintype "bidirectional"))
      (node (ref "U76") (pin "1") (pinfunction "VCC_1") (pintype "bidirectional"))
      (node (ref "U77") (pin "1") (pinfunction "VCC_1") (pintype "bidirectional"))
    )
    (net (code "80") (name "GND") (class "Default")
      (node (ref "C1") (pin "2") (pinfunction "2_2") (pintype "passive"))
      (node (ref "C10") (pin "2") (pinfunction "2_2") (pintype "passive"))
      (node (ref "C2") (pin "2") (pinfunction "2_2") (pintype "passive"))
      (node (ref "C3") (pin "2") (pinfunction "2_2") (pintype "passive"))
      (node (ref "C4") (pin "2") (pinfunction "2_2") (pintype "passive"))
      (node (ref "C5") (pin "2") (pinfunction "2_2") (pintype "passive"))
      (node (ref "C6") (pin "2") (pinfunction "2_2") (pintype "passive"))
      (node (ref "C7") (pin "2") (pinfunction "2_2") (pintype "passive"))
      (node (ref "C8") (pin "2") (pinfunction "2_2") (pintype "passive"))
      (node (ref "C9") (pin "2") (pinfunction "2_2") (pintype "passive"))
      (node (ref "J1") (pin "8") (pinfunction "8_8") (pintype "passive"))
      (node (ref "U00") (pin "3") (pinfunction "GND_3") (pintype "bidirectional"))
      (node (ref "U01") (pin "3") (pinfunction "GND_3") (pintype "bidirectional"))
      (node (ref "U02") (pin "3") (pinfunction "GND_3") (pintype "bidirectional"))
      (node (ref "U03") (pin "3") (pinfunction "GND_3") (pintype "bidirectional"))
      (node (ref "U04") (pin "3") (pinfunction "GND_3") (pintype "bidirectional"))
      (node (ref "U05") (pin "3") (pinfunction "GND_3") (pintype "bidirectional"))
      (node (ref "U06") (pin "3") (pinfunction "GND_3") (pintype "bidirectional"))
      (node (ref "U07") (pin "3") (pinfunction "GND_3") (pintype "bidirectional"))
      (node (ref "U10") (pin "3") (pinfunction "GND_3") (pintype "bidirectional"))
      (node (ref "U100") (pin "12") (pinfunction "GND_12") (pintype "bidirectional"))
      (node (ref "U101") (pin "12") (pinfunction "GND_12") (pintype "bidirectional"))
      (node (ref "U102") (pin "12") (pinfunction "GND_12") (pintype "bidirectional"))
      (node (ref "U103") (pin "12") (pinfunction "GND_12") (pintype "bidirectional"))
      (node (ref "U104") (pin "12") (pinfunction "CCKEN#_12") (pintype "bidirectional"))
      (node (ref "U104") (pin "14") (pinfunction "OE#_14") (pintype "bidirectional"))
      (node (ref "U104") (pin "8") (pinfunction "GND_8") (pintype "bidirectional"))
      (node (ref "U105") (pin "4") (pinfunction "GND_4") (pintype "bidirectional"))
      (node (ref "U106") (pin "2") (pinfunction "GND_2") (pintype "bidirectional"))
      (node (ref "U11") (pin "3") (pinfunction "GND_3") (pintype "bidirectional"))
      (node (ref "U12") (pin "3") (pinfunction "GND_3") (pintype "bidirectional"))
      (node (ref "U13") (pin "3") (pinfunction "GND_3") (pintype "bidirectional"))
      (node (ref "U14") (pin "3") (pinfunction "GND_3") (pintype "bidirectional"))
      (node (ref "U15") (pin "3") (pinfunction "GND_3") (pintype "bidirectional"))
      (node (ref "U16") (pin "3") (pinfunction "GND_3") (pintype "bidirectional"))
      (node (ref "U17") (pin "3") (pinfunction "GND_3") (pintype "bidirectional"))
      (node (ref "U20") (pin "3") (pinfunction "GND_3") (pintype "bidirectional"))
      (node (ref "U21") (pin "3") (pinfunction "GND_3") (pintype "bidirectional"))
      (node (ref "U22") (pin "3") (pinfunction "GND_3") (pintype "bidirectional"))
      (node (ref "U23") (pin "3") (pinfunction "GND_3") (pintype "bidirectional"))
      (node (ref "U24") (pin "3") (pinfunction "GND_3") (pintype "bidirectional"))
      (node (ref "U25") (pin "3") (pinfunction "GND_3") (pintype "bidirectional"))
      (node (ref "U26") (pin "3") (pinfunction "GND_3") (pintype "bidirectional"))
      (node (ref "U27") (pin "3") (pinfunction "GND_3") (pintype "bidirectional"))
      (node (ref "U30") (pin "3") (pinfunction "GND_3") (pintype "bidirectional"))
      (node (ref "U31") (pin "3") (pinfunction "GND_3") (pintype "bidirectional"))
      (node (ref "U32") (pin "3") (pinfunction "GND_3") (pintype "bidirectional"))
      (node (ref "U33") (pin "3") (pinfunction "GND_3") (pintype "bidirectional"))
      (node (ref "U34") (pin "3") (pinfunction "GND_3") (pintype "bidirectional"))
      (node (ref "U35") (pin "3") (pinfunction "GND_3") (pintype "bidirectional"))
      (node (ref "U36") (pin "3") (pinfunction "GND_3") (pintype "bidirectional"))
      (node (ref "U37") (pin "3") (pinfunction "GND_3") (pintype "bidirectional"))
      (node (ref "U40") (pin "3") (pinfunction "GND_3") (pintype "bidirectional"))
      (node (ref "U41") (pin "3") (pinfunction "GND_3") (pintype "bidirectional"))
      (node (ref "U42") (pin "3") (pinfunction "GND_3") (pintype "bidirectional"))
      (node (ref "U43") (pin "3") (pinfunction "GND_3") (pintype "bidirectional"))
      (node (ref "U44") (pin "3") (pinfunction "GND_3") (pintype "bidirectional"))
      (node (ref "U45") (pin "3") (pinfunction "GND_3") (pintype "bidirectional"))
      (node (ref "U46") (pin "3") (pinfunction "GND_3") (pintype "bidirectional"))
      (node (ref "U47") (pin "3") (pinfunction "GND_3") (pintype "bidirectional"))
      (node (ref "U50") (pin "3") (pinfunction "GND_3") (pintype "bidirectional"))
      (node (ref "U51") (pin "3") (pinfunction "GND_3") (pintype "bidirectional"))
      (node (ref "U52") (pin "3") (pinfunction "GND_3") (pintype "bidirectional"))
      (node (ref "U53") (pin "3") (pinfunction "GND_3") (pintype "bidirectional"))
      (node (ref "U54") (pin "3") (pinfunction "GND_3") (pintype "bidirectional"))
      (node (ref "U55") (pin "3") (pinfunction "GND_3") (pintype "bidirectional"))
      (node (ref "U56") (pin "3") (pinfunction "GND_3") (pintype "bidirectional"))
      (node (ref "U57") (pin "3") (pinfunction "GND_3") (pintype "bidirectional"))
      (node (ref "U60") (pin "3") (pinfunction "GND_3") (pintype "bidirectional"))
      (node (ref "U61") (pin "3") (pinfunction "GND_3") (pintype "bidirectional"))
      (node (ref "U62") (pin "3") (pinfunction "GND_3") (pintype "bidirectional"))
      (node (ref "U63") (pin "3") (pinfunction "GND_3") (pintype "bidirectional"))
      (node (ref "U64") (pin "3") (pinfunction "GND_3") (pintype "bidirectional"))
      (node (ref "U65") (pin "3") (pinfunction "GND_3") (pintype "bidirectional"))
      (node (ref "U66") (pin "3") (pinfunction "GND_3") (pintype "bidirectional"))
      (node (ref "U67") (pin "3") (pinfunction "GND_3") (pintype "bidirectional"))
      (node (ref "U70") (pin "3") (pinfunction "GND_3") (pintype "bidirectional"))
      (node (ref "U71") (pin "3") (pinfunction "GND_3") (pintype "bidirectional"))
      (node (ref "U72") (pin "3") (pinfunction "GND_3") (pintype "bidirectional"))
      (node (ref "U73") (pin "3") (pinfunction "GND_3") (pintype "bidirectional"))
      (node (ref "U74") (pin "3") (pinfunction "GND_3") (pintype "bidirectional"))
      (node (ref "U75") (pin "3") (pinfunction "GND_3") (pintype "bidirectional"))
      (node (ref "U76") (pin "3") (pinfunction "GND_3") (pintype "bidirectional"))
      (node (ref "U77") (pin "3") (pinfunction "GND_3") (pintype "bidirectional"))
    )
    (net (code "81") (name "Net-(U104-Q4)") (class "Default")
      (node (ref "U104") (pin "4") (pinfunction "Q4_4") (pintype "bidirectional"))
      (node (ref "U105") (pin "1") (pinfunction "A_1") (pintype "bidirectional"))
    )
    (net (code "82") (name "Net-(U104-Q5)") (class "Default")
      (node (ref "U104") (pin "5") (pinfunction "Q5_5") (pintype "bidirectional"))
      (node (ref "U105") (pin "2") (pinfunction "B_2") (pintype "bidirectional"))
    )
    (net (code "83") (name "unconnected-(U104-Q6-Pad6)") (class "Default")
      (node (ref "U104") (pin "6") (pinfunction "Q6_6") (pintype "bidirectional"))
    )
    (net (code "84") (name "unconnected-(U104-Q7-Pad7)") (class "Default")
      (node (ref "U104") (pin "7") (pinfunction "Q7_7") (pintype "bidirectional"))
    )
    (net (code "85") (name "unconnected-(U104-RCO#-Pad9)") (class "Default")
      (node (ref "U104") (pin "9") (pinfunction "RCO#_9") (pintype "bidirectional"))
    )
  )
)
